# sram_v3.net
KiCad netlist of a schematic drawn in EAGLE
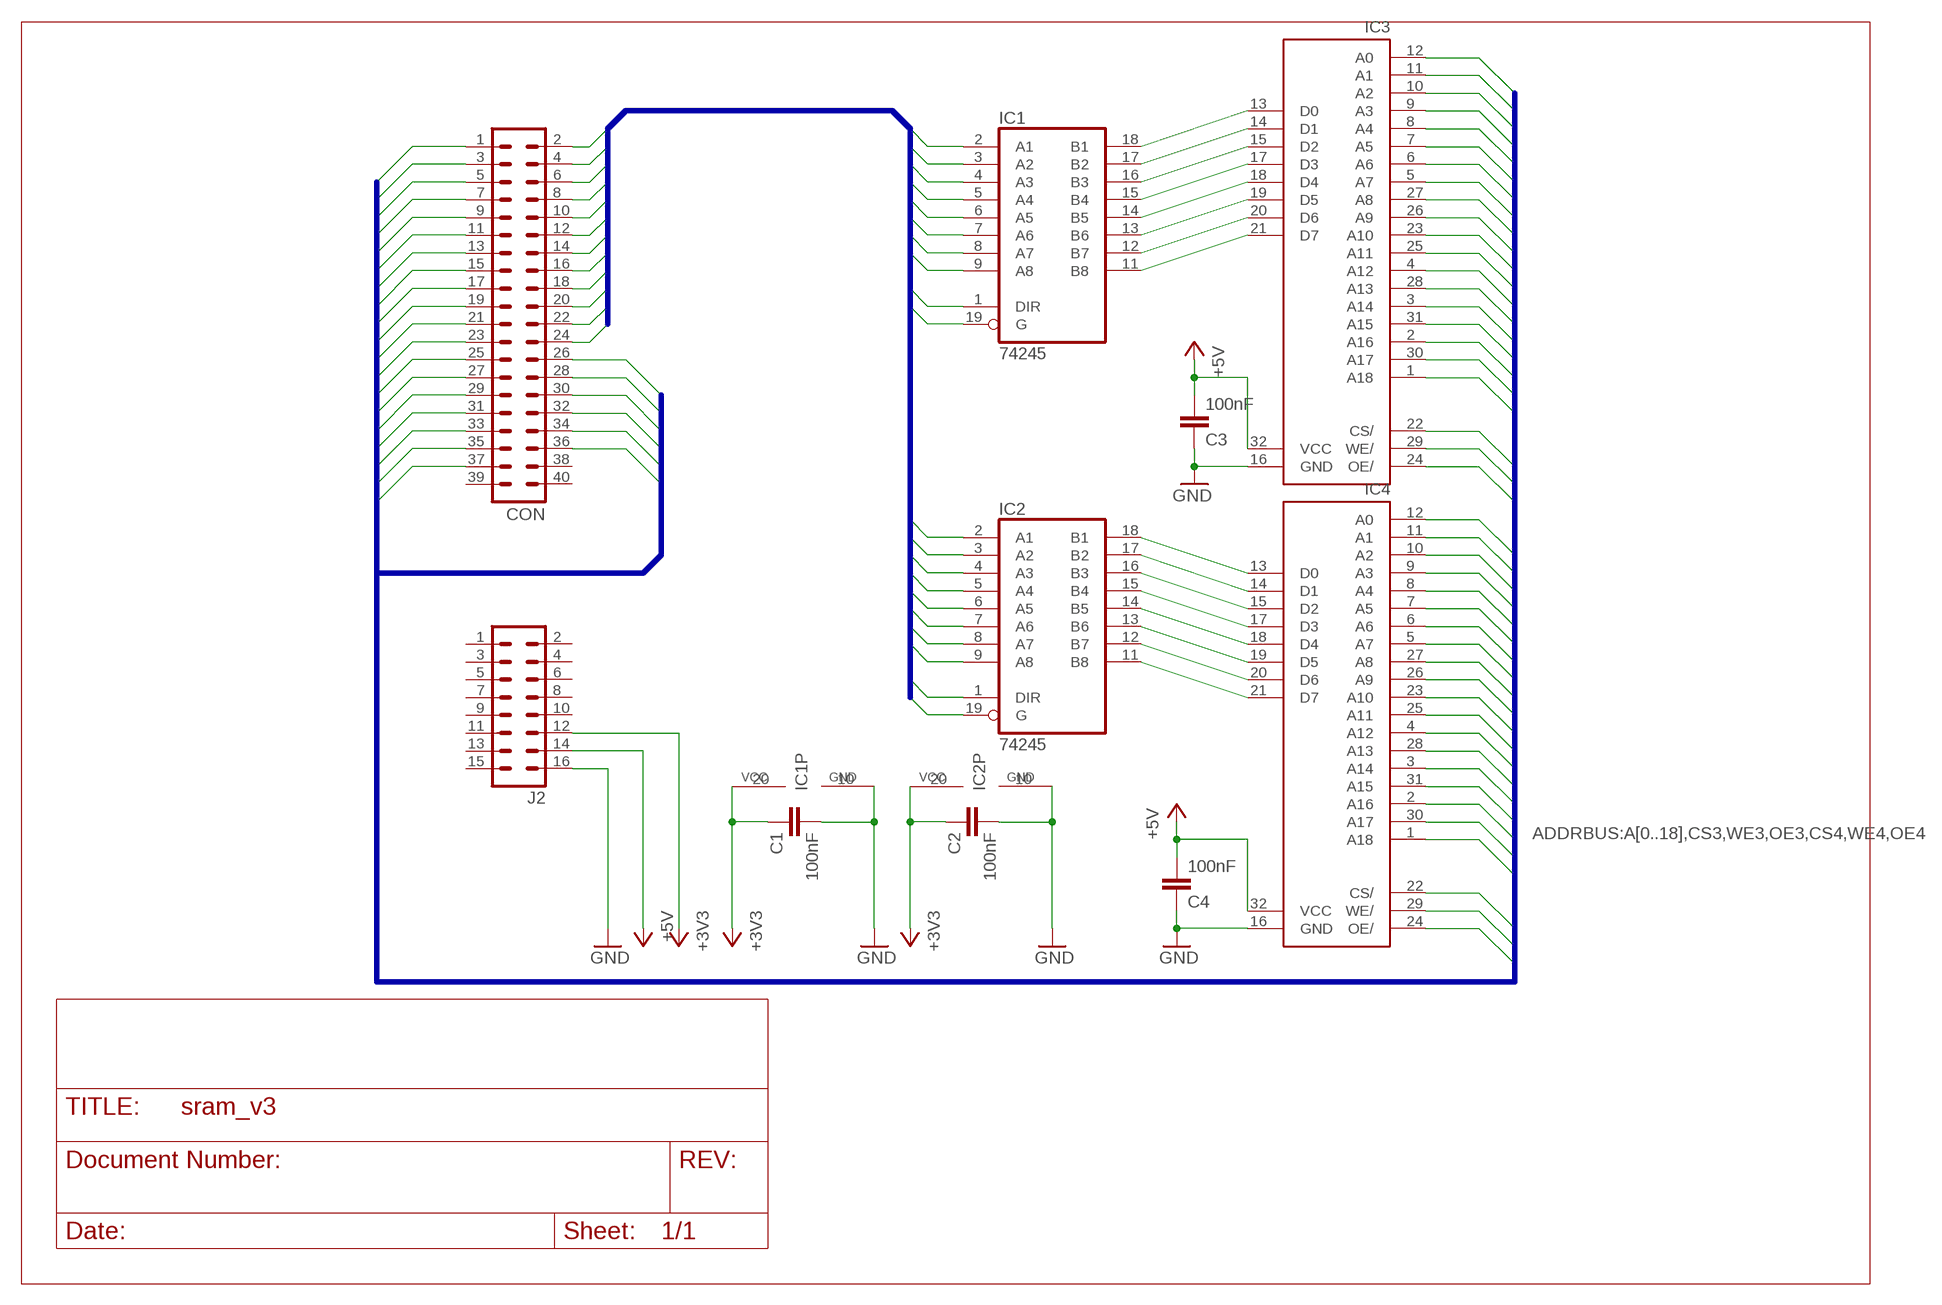
[diagram p0: schematic, sheet 1]

(export (version "E")
  (design (tool "Eeschema 10.0.6"))
  (components
    (comp (ref "C1")
      (value "100nF")
      (footprint "eagle-import:C050-030X075")
      (libsource (lib "eagle-import") (part "C-EU050-030X075"))
    )
    (comp (ref "C2")
      (value "100nF")
      (footprint "eagle-import:C050-030X075")
      (libsource (lib "eagle-import") (part "C-EU050-030X075"))
    )
    (comp (ref "C3")
      (value "100nF")
      (footprint "eagle-import:C050-030X075")
      (libsource (lib "eagle-import") (part "C-EU050-030X075"))
    )
    (comp (ref "C4")
      (value "100nF")
      (footprint "eagle-import:C050-030X075")
      (libsource (lib "eagle-import") (part "C-EU050-030X075"))
    )
    (comp (ref "CON")
      (value "ML40")
      (footprint "eagle-import:ML40")
      (libsource (lib "eagle-import") (part "ML40"))
    )
    (comp (ref "IC1")
      (value "74245")
      (footprint "eagle-import:TSSOP20")
      (libsource (lib "eagle-import") (part "74245"))
    )
    (comp (ref "IC2")
      (value "74245")
      (footprint "eagle-import:TSSOP20")
      (libsource (lib "eagle-import") (part "74245"))
    )
    (comp (ref "IC3")
      (value "MEMORY-SAMSUNG-2_KM628512-XX")
      (footprint "eagle-import:MEMORY-SAMSUNG-2_SOP-32")
      (libsource (lib "eagle-import") (part "MEMORY-SAMSUNG-2_KM628512-XX"))
    )
    (comp (ref "IC4")
      (value "MEMORY-SAMSUNG-2_KM628512-XX")
      (footprint "eagle-import:MEMORY-SAMSUNG-2_SOP-32")
      (libsource (lib "eagle-import") (part "MEMORY-SAMSUNG-2_KM628512-XX"))
    )
    (comp (ref "J2")
      (value "ML16")
      (footprint "eagle-import:ML16")
      (libsource (lib "eagle-import") (part "ML16"))
    )
  )
  (nets
    (net (code "1") (name "+3V3") (class "Default")
      (node (ref "C1") (pin "1") (pinfunction "1_1") (pintype "passive"))
      (node (ref "C2") (pin "1") (pinfunction "1_1") (pintype "passive"))
      (node (ref "IC1") (pin "20") (pinfunction "VCC_20") (pintype "power_in"))
      (node (ref "IC2") (pin "20") (pinfunction "VCC_20") (pintype "power_in"))
      (node (ref "J2") (pin "12") (pinfunction "12_12") (pintype "passive"))
    )
    (net (code "2") (name "+5V") (class "Default")
      (node (ref "C3") (pin "2") (pinfunction "2_2") (pintype "passive"))
      (node (ref "C4") (pin "2") (pinfunction "2_2") (pintype "passive"))
      (node (ref "IC3") (pin "32") (pinfunction "VCC_32") (pintype "power_in"))
      (node (ref "IC4") (pin "32") (pinfunction "VCC_32") (pintype "power_in"))
      (node (ref "J2") (pin "14") (pinfunction "14_14") (pintype "passive"))
    )
    (net (code "3") (name "/A0") (class "Default")
      (node (ref "CON") (pin "37") (pinfunction "37_37") (pintype "passive"))
      (node (ref "IC3") (pin "12") (pinfunction "A0_12") (pintype "input"))
      (node (ref "IC4") (pin "12") (pinfunction "A0_12") (pintype "input"))
    )
    (net (code "4") (name "/A1") (class "Default")
      (node (ref "CON") (pin "35") (pinfunction "35_35") (pintype "passive"))
      (node (ref "IC3") (pin "11") (pinfunction "A1_11") (pintype "input"))
      (node (ref "IC4") (pin "11") (pinfunction "A1_11") (pintype "input"))
    )
    (net (code "5") (name "/A2") (class "Default")
      (node (ref "CON") (pin "33") (pinfunction "33_33") (pintype "passive"))
      (node (ref "IC3") (pin "10") (pinfunction "A2_10") (pintype "input"))
      (node (ref "IC4") (pin "10") (pinfunction "A2_10") (pintype "input"))
    )
    (net (code "6") (name "/A3") (class "Default")
      (node (ref "CON") (pin "31") (pinfunction "31_31") (pintype "passive"))
      (node (ref "IC3") (pin "9") (pinfunction "A3_9") (pintype "input"))
      (node (ref "IC4") (pin "9") (pinfunction "A3_9") (pintype "input"))
    )
    (net (code "7") (name "/A4") (class "Default")
      (node (ref "CON") (pin "29") (pinfunction "29_29") (pintype "passive"))
      (node (ref "IC3") (pin "8") (pinfunction "A4_8") (pintype "input"))
      (node (ref "IC4") (pin "8") (pinfunction "A4_8") (pintype "input"))
    )
    (net (code "8") (name "/A5") (class "Default")
      (node (ref "CON") (pin "27") (pinfunction "27_27") (pintype "passive"))
      (node (ref "IC3") (pin "7") (pinfunction "A5_7") (pintype "input"))
      (node (ref "IC4") (pin "7") (pinfunction "A5_7") (pintype "input"))
    )
    (net (code "9") (name "/A6") (class "Default")
      (node (ref "CON") (pin "25") (pinfunction "25_25") (pintype "passive"))
      (node (ref "IC3") (pin "6") (pinfunction "A6_6") (pintype "input"))
      (node (ref "IC4") (pin "6") (pinfunction "A6_6") (pintype "input"))
    )
    (net (code "10") (name "/A7") (class "Default")
      (node (ref "CON") (pin "23") (pinfunction "23_23") (pintype "passive"))
      (node (ref "IC3") (pin "5") (pinfunction "A7_5") (pintype "input"))
      (node (ref "IC4") (pin "5") (pinfunction "A7_5") (pintype "input"))
    )
    (net (code "11") (name "/A8") (class "Default")
      (node (ref "CON") (pin "21") (pinfunction "21_21") (pintype "passive"))
      (node (ref "IC3") (pin "27") (pinfunction "A8_27") (pintype "input"))
      (node (ref "IC4") (pin "27") (pinfunction "A8_27") (pintype "input"))
    )
    (net (code "12") (name "/A9") (class "Default")
      (node (ref "CON") (pin "19") (pinfunction "19_19") (pintype "passive"))
      (node (ref "IC3") (pin "26") (pinfunction "A9_26") (pintype "input"))
      (node (ref "IC4") (pin "26") (pinfunction "A9_26") (pintype "input"))
    )
    (net (code "13") (name "/A10") (class "Default")
      (node (ref "CON") (pin "17") (pinfunction "17_17") (pintype "passive"))
      (node (ref "IC3") (pin "23") (pinfunction "A10_23") (pintype "input"))
      (node (ref "IC4") (pin "23") (pinfunction "A10_23") (pintype "input"))
    )
    (net (code "14") (name "/A11") (class "Default")
      (node (ref "CON") (pin "15") (pinfunction "15_15") (pintype "passive"))
      (node (ref "IC3") (pin "25") (pinfunction "A11_25") (pintype "input"))
      (node (ref "IC4") (pin "25") (pinfunction "A11_25") (pintype "input"))
    )
    (net (code "15") (name "/A12") (class "Default")
      (node (ref "CON") (pin "13") (pinfunction "13_13") (pintype "passive"))
      (node (ref "IC3") (pin "4") (pinfunction "A12_4") (pintype "input"))
      (node (ref "IC4") (pin "4") (pinfunction "A12_4") (pintype "input"))
    )
    (net (code "16") (name "/A13") (class "Default")
      (node (ref "CON") (pin "11") (pinfunction "11_11") (pintype "passive"))
      (node (ref "IC3") (pin "28") (pinfunction "A13_28") (pintype "input"))
      (node (ref "IC4") (pin "28") (pinfunction "A13_28") (pintype "input"))
    )
    (net (code "17") (name "/A14") (class "Default")
      (node (ref "CON") (pin "9") (pinfunction "9_9") (pintype "passive"))
      (node (ref "IC3") (pin "3") (pinfunction "A14_3") (pintype "input"))
      (node (ref "IC4") (pin "3") (pinfunction "A14_3") (pintype "input"))
    )
    (net (code "18") (name "/A15") (class "Default")
      (node (ref "CON") (pin "7") (pinfunction "7_7") (pintype "passive"))
      (node (ref "IC3") (pin "31") (pinfunction "A15_31") (pintype "input"))
      (node (ref "IC4") (pin "31") (pinfunction "A15_31") (pintype "input"))
    )
    (net (code "19") (name "/A16") (class "Default")
      (node (ref "CON") (pin "5") (pinfunction "5_5") (pintype "passive"))
      (node (ref "IC3") (pin "2") (pinfunction "A16_2") (pintype "input"))
      (node (ref "IC4") (pin "2") (pinfunction "A16_2") (pintype "input"))
    )
    (net (code "20") (name "/A17") (class "Default")
      (node (ref "CON") (pin "3") (pinfunction "3_3") (pintype "passive"))
      (node (ref "IC3") (pin "30") (pinfunction "A17_30") (pintype "input"))
      (node (ref "IC4") (pin "30") (pinfunction "A17_30") (pintype "input"))
    )
    (net (code "21") (name "/A18") (class "Default")
      (node (ref "CON") (pin "1") (pinfunction "1_1") (pintype "passive"))
      (node (ref "IC3") (pin "1") (pinfunction "A18_1") (pintype "input"))
      (node (ref "IC4") (pin "1") (pinfunction "A18_1") (pintype "input"))
    )
    (net (code "22") (name "/CS3") (class "Default")
      (node (ref "CON") (pin "26") (pinfunction "26_26") (pintype "passive"))
      (node (ref "IC3") (pin "22") (pinfunction "CS/_22") (pintype "input"))
    )
    (net (code "23") (name "/CS4") (class "Default")
      (node (ref "CON") (pin "32") (pinfunction "32_32") (pintype "passive"))
      (node (ref "IC4") (pin "22") (pinfunction "CS/_22") (pintype "input"))
    )
    (net (code "24") (name "/D0") (class "Default")
      (node (ref "CON") (pin "16") (pinfunction "16_16") (pintype "passive"))
      (node (ref "IC1") (pin "2") (pinfunction "A1_2") (pintype "bidirectional"))
      (node (ref "IC2") (pin "2") (pinfunction "A1_2") (pintype "bidirectional"))
    )
    (net (code "25") (name "/D1") (class "Default")
      (node (ref "CON") (pin "14") (pinfunction "14_14") (pintype "passive"))
      (node (ref "IC1") (pin "3") (pinfunction "A2_3") (pintype "bidirectional"))
      (node (ref "IC2") (pin "3") (pinfunction "A2_3") (pintype "bidirectional"))
    )
    (net (code "26") (name "/D2") (class "Default")
      (node (ref "CON") (pin "12") (pinfunction "12_12") (pintype "passive"))
      (node (ref "IC1") (pin "4") (pinfunction "A3_4") (pintype "bidirectional"))
      (node (ref "IC2") (pin "4") (pinfunction "A3_4") (pintype "bidirectional"))
    )
    (net (code "27") (name "/D3") (class "Default")
      (node (ref "CON") (pin "10") (pinfunction "10_10") (pintype "passive"))
      (node (ref "IC1") (pin "5") (pinfunction "A4_5") (pintype "bidirectional"))
      (node (ref "IC2") (pin "5") (pinfunction "A4_5") (pintype "bidirectional"))
    )
    (net (code "28") (name "/D4") (class "Default")
      (node (ref "CON") (pin "8") (pinfunction "8_8") (pintype "passive"))
      (node (ref "IC1") (pin "6") (pinfunction "A5_6") (pintype "bidirectional"))
      (node (ref "IC2") (pin "6") (pinfunction "A5_6") (pintype "bidirectional"))
    )
    (net (code "29") (name "/D5") (class "Default")
      (node (ref "CON") (pin "6") (pinfunction "6_6") (pintype "passive"))
      (node (ref "IC1") (pin "7") (pinfunction "A6_7") (pintype "bidirectional"))
      (node (ref "IC2") (pin "7") (pinfunction "A6_7") (pintype "bidirectional"))
    )
    (net (code "30") (name "/D6") (class "Default")
      (node (ref "CON") (pin "4") (pinfunction "4_4") (pintype "passive"))
      (node (ref "IC1") (pin "8") (pinfunction "A7_8") (pintype "bidirectional"))
      (node (ref "IC2") (pin "8") (pinfunction "A7_8") (pintype "bidirectional"))
    )
    (net (code "31") (name "/D7") (class "Default")
      (node (ref "CON") (pin "2") (pinfunction "2_2") (pintype "passive"))
      (node (ref "IC1") (pin "9") (pinfunction "A8_9") (pintype "bidirectional"))
      (node (ref "IC2") (pin "9") (pinfunction "A8_9") (pintype "bidirectional"))
    )
    (net (code "32") (name "/DIR1") (class "Default")
      (node (ref "CON") (pin "18") (pinfunction "18_18") (pintype "passive"))
      (node (ref "IC1") (pin "1") (pinfunction "DIR_1") (pintype "input"))
    )
    (net (code "33") (name "/DIR2") (class "Default")
      (node (ref "CON") (pin "22") (pinfunction "22_22") (pintype "passive"))
      (node (ref "IC2") (pin "1") (pinfunction "DIR_1") (pintype "input"))
    )
    (net (code "34") (name "/G1") (class "Default")
      (node (ref "CON") (pin "20") (pinfunction "20_20") (pintype "passive"))
      (node (ref "IC1") (pin "19") (pinfunction "G_19") (pintype "input"))
    )
    (net (code "35") (name "/G2") (class "Default")
      (node (ref "CON") (pin "24") (pinfunction "24_24") (pintype "passive"))
      (node (ref "IC2") (pin "19") (pinfunction "G_19") (pintype "input"))
    )
    (net (code "36") (name "/OE3") (class "Default")
      (node (ref "CON") (pin "30") (pinfunction "30_30") (pintype "passive"))
      (node (ref "IC3") (pin "24") (pinfunction "OE/_24") (pintype "input"))
    )
    (net (code "37") (name "/OE4") (class "Default")
      (node (ref "CON") (pin "36") (pinfunction "36_36") (pintype "passive"))
      (node (ref "IC4") (pin "24") (pinfunction "OE/_24") (pintype "input"))
    )
    (net (code "38") (name "/WE3") (class "Default")
      (node (ref "CON") (pin "28") (pinfunction "28_28") (pintype "passive"))
      (node (ref "IC3") (pin "29") (pinfunction "WE/_29") (pintype "input"))
    )
    (net (code "39") (name "/WE4") (class "Default")
      (node (ref "CON") (pin "34") (pinfunction "34_34") (pintype "passive"))
      (node (ref "IC4") (pin "29") (pinfunction "WE/_29") (pintype "input"))
    )
    (net (code "41") (name "GND") (class "Default")
      (node (ref "C1") (pin "2") (pinfunction "2_2") (pintype "passive"))
      (node (ref "C2") (pin "2") (pinfunction "2_2") (pintype "passive"))
      (node (ref "C3") (pin "1") (pinfunction "1_1") (pintype "passive"))
      (node (ref "C4") (pin "1") (pinfunction "1_1") (pintype "passive"))
      (node (ref "IC1") (pin "10") (pinfunction "GND_10") (pintype "power_in"))
      (node (ref "IC2") (pin "10") (pinfunction "GND_10") (pintype "power_in"))
      (node (ref "IC3") (pin "16") (pinfunction "GND_16") (pintype "power_in"))
      (node (ref "IC4") (pin "16") (pinfunction "GND_16") (pintype "power_in"))
      (node (ref "J2") (pin "16") (pinfunction "16_16") (pintype "passive"))
    )
    (net (code "42") (name "Net-(IC1A-B1)") (class "Default")
      (node (ref "IC1") (pin "18") (pinfunction "B1_18") (pintype "bidirectional"))
      (node (ref "IC3") (pin "13") (pinfunction "D0_13") (pintype "tri_state"))
    )
    (net (code "43") (name "Net-(IC1A-B2)") (class "Default")
      (node (ref "IC1") (pin "17") (pinfunction "B2_17") (pintype "bidirectional"))
      (node (ref "IC3") (pin "14") (pinfunction "D1_14") (pintype "tri_state"))
    )
    (net (code "44") (name "Net-(IC1A-B3)") (class "Default")
      (node (ref "IC1") (pin "16") (pinfunction "B3_16") (pintype "bidirectional"))
      (node (ref "IC3") (pin "15") (pinfunction "D2_15") (pintype "tri_state"))
    )
    (net (code "45") (name "Net-(IC1A-B4)") (class "Default")
      (node (ref "IC1") (pin "15") (pinfunction "B4_15") (pintype "bidirectional"))
      (node (ref "IC3") (pin "17") (pinfunction "D3_17") (pintype "tri_state"))
    )
    (net (code "46") (name "Net-(IC1A-B5)") (class "Default")
      (node (ref "IC1") (pin "14") (pinfunction "B5_14") (pintype "bidirectional"))
      (node (ref "IC3") (pin "18") (pinfunction "D4_18") (pintype "tri_state"))
    )
    (net (code "47") (name "Net-(IC1A-B6)") (class "Default")
      (node (ref "IC1") (pin "13") (pinfunction "B6_13") (pintype "bidirectional"))
      (node (ref "IC3") (pin "19") (pinfunction "D5_19") (pintype "tri_state"))
    )
    (net (code "48") (name "Net-(IC1A-B7)") (class "Default")
      (node (ref "IC1") (pin "12") (pinfunction "B7_12") (pintype "bidirectional"))
      (node (ref "IC3") (pin "20") (pinfunction "D6_20") (pintype "tri_state"))
    )
    (net (code "49") (name "Net-(IC1A-B8)") (class "Default")
      (node (ref "IC1") (pin "11") (pinfunction "B8_11") (pintype "bidirectional"))
      (node (ref "IC3") (pin "21") (pinfunction "D7_21") (pintype "tri_state"))
    )
    (net (code "50") (name "Net-(IC2A-B1)") (class "Default")
      (node (ref "IC2") (pin "18") (pinfunction "B1_18") (pintype "bidirectional"))
      (node (ref "IC4") (pin "13") (pinfunction "D0_13") (pintype "tri_state"))
    )
    (net (code "51") (name "Net-(IC2A-B2)") (class "Default")
      (node (ref "IC2") (pin "17") (pinfunction "B2_17") (pintype "bidirectional"))
      (node (ref "IC4") (pin "14") (pinfunction "D1_14") (pintype "tri_state"))
    )
    (net (code "52") (name "Net-(IC2A-B3)") (class "Default")
      (node (ref "IC2") (pin "16") (pinfunction "B3_16") (pintype "bidirectional"))
      (node (ref "IC4") (pin "15") (pinfunction "D2_15") (pintype "tri_state"))
    )
    (net (code "53") (name "Net-(IC2A-B4)") (class "Default")
      (node (ref "IC2") (pin "15") (pinfunction "B4_15") (pintype "bidirectional"))
      (node (ref "IC4") (pin "17") (pinfunction "D3_17") (pintype "tri_state"))
    )
    (net (code "54") (name "Net-(IC2A-B5)") (class "Default")
      (node (ref "IC2") (pin "14") (pinfunction "B5_14") (pintype "bidirectional"))
      (node (ref "IC4") (pin "18") (pinfunction "D4_18") (pintype "tri_state"))
    )
    (net (code "55") (name "Net-(IC2A-B6)") (class "Default")
      (node (ref "IC2") (pin "13") (pinfunction "B6_13") (pintype "bidirectional"))
      (node (ref "IC4") (pin "19") (pinfunction "D5_19") (pintype "tri_state"))
    )
    (net (code "56") (name "Net-(IC2A-B7)") (class "Default")
      (node (ref "IC2") (pin "12") (pinfunction "B7_12") (pintype "bidirectional"))
      (node (ref "IC4") (pin "20") (pinfunction "D6_20") (pintype "tri_state"))
    )
    (net (code "57") (name "Net-(IC2A-B8)") (class "Default")
      (node (ref "IC2") (pin "11") (pinfunction "B8_11") (pintype "bidirectional"))
      (node (ref "IC4") (pin "21") (pinfunction "D7_21") (pintype "tri_state"))
    )
    (net (code "58") (name "unconnected-(CON-Pad38)") (class "Default")
      (node (ref "CON") (pin "38") (pinfunction "38_38") (pintype "passive"))
    )
    (net (code "59") (name "unconnected-(CON-Pad39)") (class "Default")
      (node (ref "CON") (pin "39") (pinfunction "39_39") (pintype "passive"))
    )
    (net (code "60") (name "unconnected-(CON-Pad40)") (class "Default")
      (node (ref "CON") (pin "40") (pinfunction "40_40") (pintype "passive"))
    )
    (net (code "61") (name "unconnected-(J2-Pad1)") (class "Default")
      (node (ref "J2") (pin "1") (pinfunction "1_1") (pintype "passive"))
    )
    (net (code "62") (name "unconnected-(J2-Pad2)") (class "Default")
      (node (ref "J2") (pin "2") (pinfunction "2_2") (pintype "passive"))
    )
    (net (code "63") (name "unconnected-(J2-Pad3)") (class "Default")
      (node (ref "J2") (pin "3") (pinfunction "3_3") (pintype "passive"))
    )
    (net (code "64") (name "unconnected-(J2-Pad4)") (class "Default")
      (node (ref "J2") (pin "4") (pinfunction "4_4") (pintype "passive"))
    )
    (net (code "65") (name "unconnected-(J2-Pad5)") (class "Default")
      (node (ref "J2") (pin "5") (pinfunction "5_5") (pintype "passive"))
    )
    (net (code "66") (name "unconnected-(J2-Pad6)") (class "Default")
      (node (ref "J2") (pin "6") (pinfunction "6_6") (pintype "passive"))
    )
    (net (code "67") (name "unconnected-(J2-Pad7)") (class "Default")
      (node (ref "J2") (pin "7") (pinfunction "7_7") (pintype "passive"))
    )
    (net (code "68") (name "unconnected-(J2-Pad8)") (class "Default")
      (node (ref "J2") (pin "8") (pinfunction "8_8") (pintype "passive"))
    )
    (net (code "69") (name "unconnected-(J2-Pad9)") (class "Default")
      (node (ref "J2") (pin "9") (pinfunction "9_9") (pintype "passive"))
    )
    (net (code "70") (name "unconnected-(J2-Pad10)") (class "Default")
      (node (ref "J2") (pin "10") (pinfunction "10_10") (pintype "passive"))
    )
    (net (code "71") (name "unconnected-(J2-Pad11)") (class "Default")
      (node (ref "J2") (pin "11") (pinfunction "11_11") (pintype "passive"))
    )
    (net (code "72") (name "unconnected-(J2-Pad13)") (class "Default")
      (node (ref "J2") (pin "13") (pinfunction "13_13") (pintype "passive"))
    )
    (net (code "73") (name "unconnected-(J2-Pad15)") (class "Default")
      (node (ref "J2") (pin "15") (pinfunction "15_15") (pintype "passive"))
    )
  )
)
